# ULA.net
KiCad netlist of a schematic drawn in EAGLE
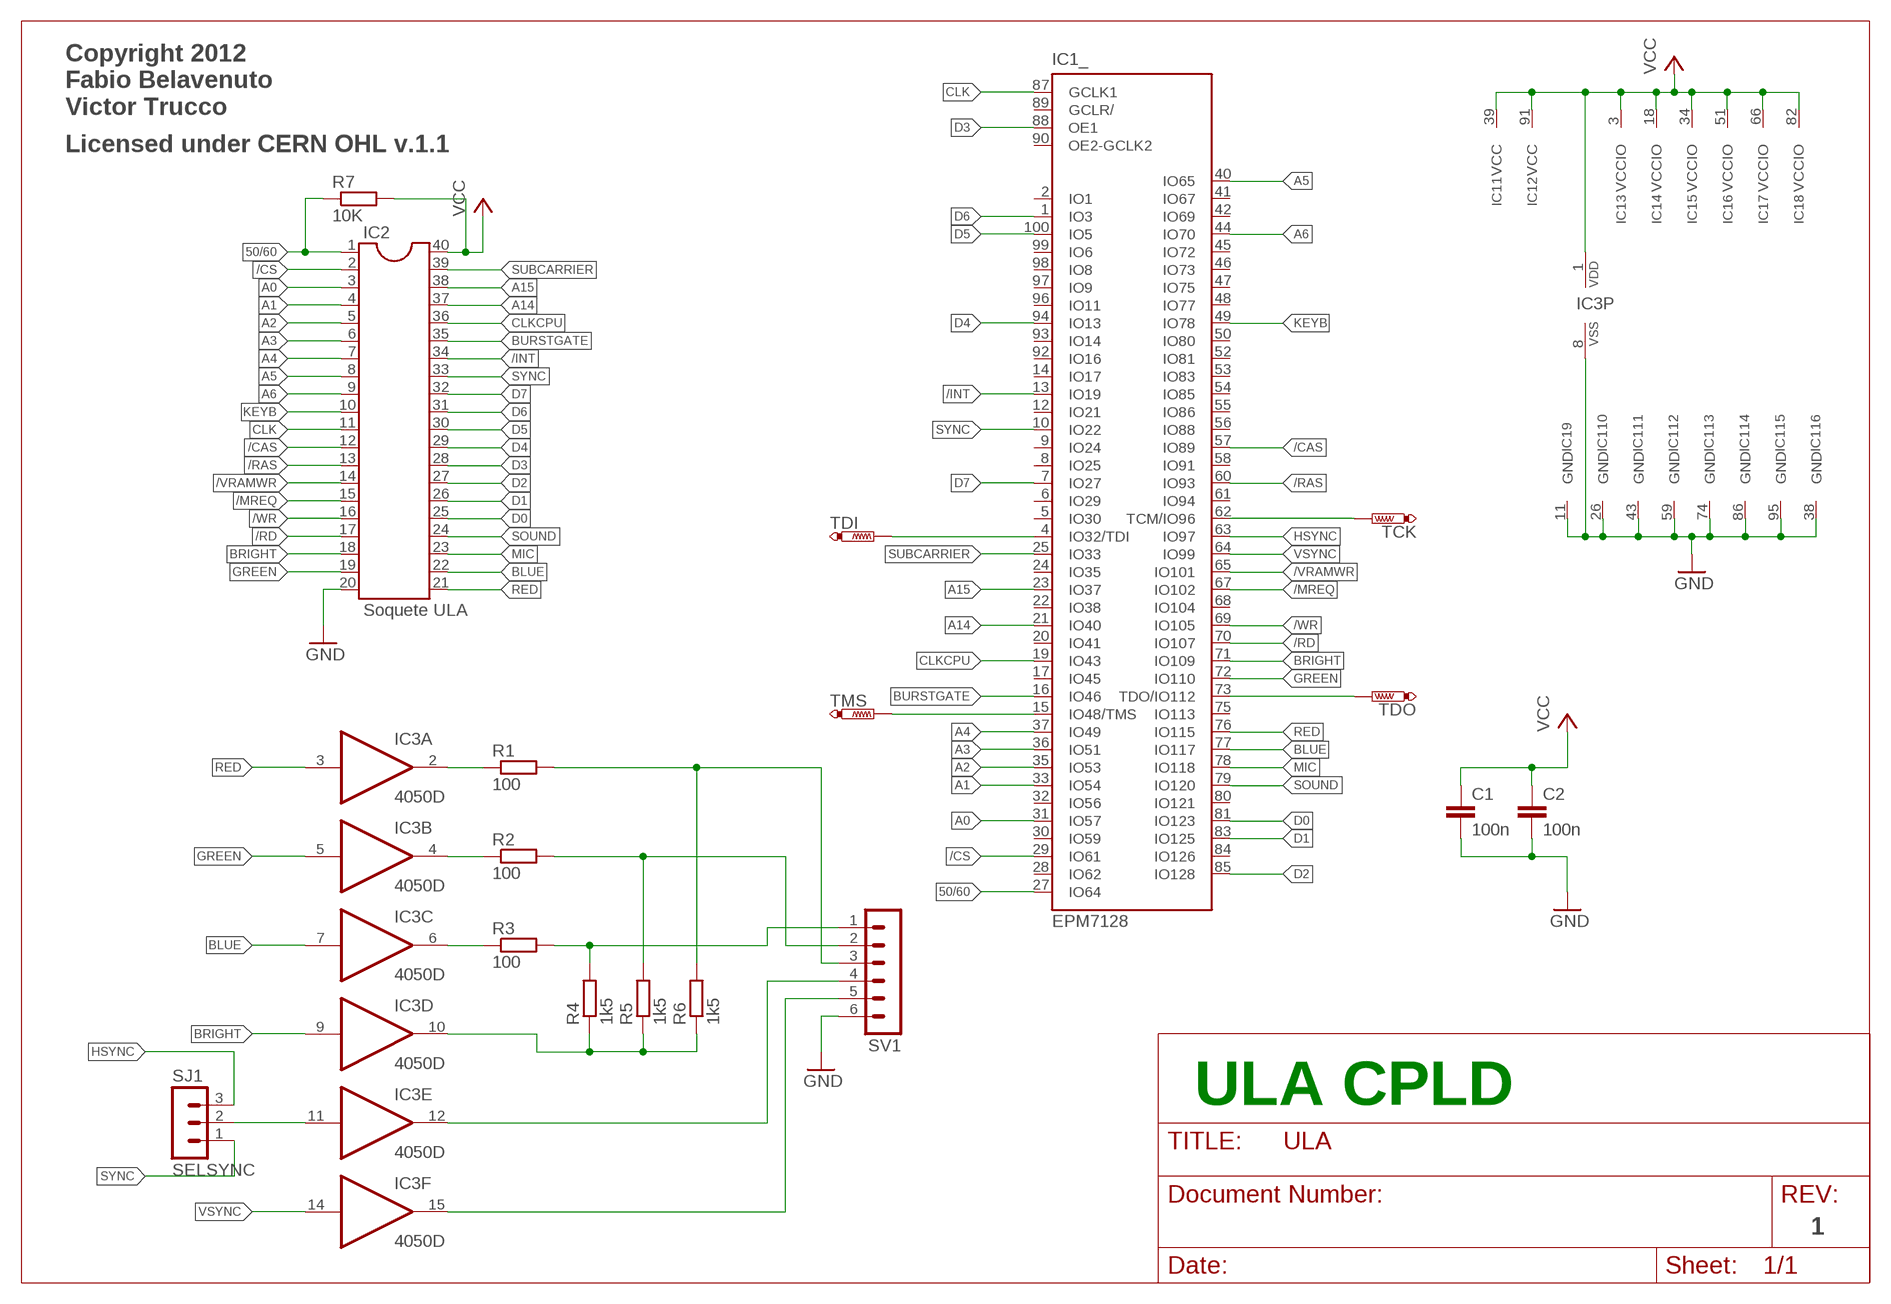
[diagram p0: schematic, sheet 1]

(export (version "E")
  (design (tool "Eeschema 10.0.6"))
  (components
    (comp (ref "C1")
      (value "100n")
      (footprint "eagle-import:C1206K")
      (libsource (lib "eagle-import") (part "C-EUC1206K"))
    )
    (comp (ref "C2")
      (value "100n")
      (footprint "eagle-import:C1206K")
      (libsource (lib "eagle-import") (part "C-EUC1206K"))
    )
    (comp (ref "IC1")
      (value "EPM7128")
      (footprint "eagle-import:TQFP100")
      (fields (field (name "MPN") "EPM7128STC100-7N"))
      (libsource (lib "eagle-import") (part "EPM7128-?100T"))
    )
    (comp (ref "IC2")
      (value "Soquete ULA")
      (footprint "eagle-import:DIL40")
      (libsource (lib "eagle-import") (part "DIL40"))
    )
    (comp (ref "IC3")
      (value "4050D")
      (footprint "eagle-import:SO16")
      (libsource (lib "eagle-import") (part "4050D"))
    )
    (comp (ref "R1")
      (value "100")
      (footprint "eagle-import:M0805")
      (libsource (lib "eagle-import") (part "R-EU_M0805"))
    )
    (comp (ref "R2")
      (value "100")
      (footprint "eagle-import:M0805")
      (libsource (lib "eagle-import") (part "R-EU_M0805"))
    )
    (comp (ref "R3")
      (value "100")
      (footprint "eagle-import:M0805")
      (libsource (lib "eagle-import") (part "R-EU_M0805"))
    )
    (comp (ref "R4")
      (value "1k5")
      (footprint "eagle-import:M0805")
      (libsource (lib "eagle-import") (part "R-EU_M0805"))
    )
    (comp (ref "R5")
      (value "1k5")
      (footprint "eagle-import:M0805")
      (libsource (lib "eagle-import") (part "R-EU_M0805"))
    )
    (comp (ref "R6")
      (value "1k5")
      (footprint "eagle-import:M0805")
      (libsource (lib "eagle-import") (part "R-EU_M0805"))
    )
    (comp (ref "R7")
      (value "10K")
      (footprint "eagle-import:M0805")
      (libsource (lib "eagle-import") (part "R-EU_M0805"))
    )
    (comp (ref "SJ1")
      (value "SELSYNC")
      (footprint "eagle-import:MA03-1-1")
      (libsource (lib "eagle-import") (part "MA03-1MA03-1-1"))
    )
    (comp (ref "SV1")
      (value "MA06-11")
      (footprint "eagle-import:MA06-1-1")
      (libsource (lib "eagle-import") (part "MA06-11"))
    )
    (comp (ref "TCK")
      (value "PTR1PAD1-10")
      (footprint "eagle-import:P1-10")
      (libsource (lib "eagle-import") (part "PTR1PAD1-10"))
    )
    (comp (ref "TDI")
      (value "PTR1PAD1-10")
      (footprint "eagle-import:P1-10")
      (libsource (lib "eagle-import") (part "PTR1PAD1-10"))
    )
    (comp (ref "TDO")
      (value "PTR1PAD1-10")
      (footprint "eagle-import:P1-10")
      (libsource (lib "eagle-import") (part "PTR1PAD1-10"))
    )
    (comp (ref "TMS")
      (value "PTR1PAD1-10")
      (footprint "eagle-import:P1-10")
      (libsource (lib "eagle-import") (part "PTR1PAD1-10"))
    )
  )
  (nets
    (net (code "1") (name "50{slash}60") (class "Default")
      (node (ref "IC1") (pin "27") (pinfunction "IO64_27") (pintype "bidirectional"))
      (node (ref "IC2") (pin "1") (pinfunction "1_1") (pintype "passive"))
      (node (ref "R7") (pin "1") (pinfunction "1_1") (pintype "passive"))
    )
    (net (code "2") (name "A0") (class "Default")
      (node (ref "IC1") (pin "31") (pinfunction "IO57_31") (pintype "bidirectional"))
      (node (ref "IC2") (pin "3") (pinfunction "3_3") (pintype "passive"))
    )
    (net (code "3") (name "A1") (class "Default")
      (node (ref "IC1") (pin "33") (pinfunction "IO54_33") (pintype "bidirectional"))
      (node (ref "IC2") (pin "4") (pinfunction "4_4") (pintype "passive"))
    )
    (net (code "4") (name "A2") (class "Default")
      (node (ref "IC1") (pin "35") (pinfunction "IO53_35") (pintype "bidirectional"))
      (node (ref "IC2") (pin "5") (pinfunction "5_5") (pintype "passive"))
    )
    (net (code "5") (name "A3") (class "Default")
      (node (ref "IC1") (pin "36") (pinfunction "IO51_36") (pintype "bidirectional"))
      (node (ref "IC2") (pin "6") (pinfunction "6_6") (pintype "passive"))
    )
    (net (code "6") (name "A4") (class "Default")
      (node (ref "IC1") (pin "37") (pinfunction "IO49_37") (pintype "bidirectional"))
      (node (ref "IC2") (pin "7") (pinfunction "7_7") (pintype "passive"))
    )
    (net (code "7") (name "A5") (class "Default")
      (node (ref "IC1") (pin "40") (pinfunction "IO65_40") (pintype "bidirectional"))
      (node (ref "IC2") (pin "8") (pinfunction "8_8") (pintype "passive"))
    )
    (net (code "8") (name "A6") (class "Default")
      (node (ref "IC1") (pin "44") (pinfunction "IO70_44") (pintype "bidirectional"))
      (node (ref "IC2") (pin "9") (pinfunction "9_9") (pintype "passive"))
    )
    (net (code "9") (name "A14") (class "Default")
      (node (ref "IC1") (pin "21") (pinfunction "IO40_21") (pintype "bidirectional"))
      (node (ref "IC2") (pin "37") (pinfunction "37_37") (pintype "passive"))
    )
    (net (code "10") (name "A15") (class "Default")
      (node (ref "IC1") (pin "23") (pinfunction "IO37_23") (pintype "bidirectional"))
      (node (ref "IC2") (pin "38") (pinfunction "38_38") (pintype "passive"))
    )
    (net (code "11") (name "BLUE") (class "Default")
      (node (ref "IC1") (pin "77") (pinfunction "IO117_77") (pintype "bidirectional"))
      (node (ref "IC2") (pin "22") (pinfunction "22_22") (pintype "passive"))
      (node (ref "IC3") (pin "7") (pinfunction "I_7") (pintype "input"))
    )
    (net (code "12") (name "BRIGHT") (class "Default")
      (node (ref "IC1") (pin "71") (pinfunction "IO109_71") (pintype "bidirectional"))
      (node (ref "IC2") (pin "18") (pinfunction "18_18") (pintype "passive"))
      (node (ref "IC3") (pin "9") (pinfunction "I_9") (pintype "input"))
    )
    (net (code "13") (name "BURSTGATE") (class "Default")
      (node (ref "IC1") (pin "16") (pinfunction "IO46_16") (pintype "bidirectional"))
      (node (ref "IC2") (pin "35") (pinfunction "35_35") (pintype "passive"))
    )
    (net (code "14") (name "CLK") (class "Default")
      (node (ref "IC1") (pin "87") (pinfunction "GCLK1_87") (pintype "input"))
      (node (ref "IC2") (pin "11") (pinfunction "11_11") (pintype "passive"))
    )
    (net (code "15") (name "CLKCPU") (class "Default")
      (node (ref "IC1") (pin "19") (pinfunction "IO43_19") (pintype "bidirectional"))
      (node (ref "IC2") (pin "36") (pinfunction "36_36") (pintype "passive"))
    )
    (net (code "16") (name "D0") (class "Default")
      (node (ref "IC1") (pin "81") (pinfunction "IO123_81") (pintype "bidirectional"))
      (node (ref "IC2") (pin "25") (pinfunction "25_25") (pintype "passive"))
    )
    (net (code "17") (name "D1") (class "Default")
      (node (ref "IC1") (pin "83") (pinfunction "IO125_83") (pintype "bidirectional"))
      (node (ref "IC2") (pin "26") (pinfunction "26_26") (pintype "passive"))
    )
    (net (code "18") (name "D2") (class "Default")
      (node (ref "IC1") (pin "85") (pinfunction "IO128_85") (pintype "bidirectional"))
      (node (ref "IC2") (pin "27") (pinfunction "27_27") (pintype "passive"))
    )
    (net (code "19") (name "D3") (class "Default")
      (node (ref "IC1") (pin "88") (pinfunction "OE1_88") (pintype "input"))
      (node (ref "IC2") (pin "28") (pinfunction "28_28") (pintype "passive"))
    )
    (net (code "20") (name "D4") (class "Default")
      (node (ref "IC1") (pin "94") (pinfunction "IO13_94") (pintype "bidirectional"))
      (node (ref "IC2") (pin "29") (pinfunction "29_29") (pintype "passive"))
    )
    (net (code "21") (name "D5") (class "Default")
      (node (ref "IC1") (pin "100") (pinfunction "IO5_100") (pintype "bidirectional"))
      (node (ref "IC2") (pin "30") (pinfunction "30_30") (pintype "passive"))
    )
    (net (code "22") (name "D6") (class "Default")
      (node (ref "IC1") (pin "1") (pinfunction "IO3_1") (pintype "bidirectional"))
      (node (ref "IC2") (pin "31") (pinfunction "31_31") (pintype "passive"))
    )
    (net (code "23") (name "D7") (class "Default")
      (node (ref "IC1") (pin "7") (pinfunction "IO27_7") (pintype "bidirectional"))
      (node (ref "IC2") (pin "32") (pinfunction "32_32") (pintype "passive"))
    )
    (net (code "24") (name "GND") (class "Default")
      (node (ref "C1") (pin "2") (pinfunction "2_2") (pintype "passive"))
      (node (ref "C2") (pin "2") (pinfunction "2_2") (pintype "passive"))
      (node (ref "IC1") (pin "11") (pinfunction "GND_11") (pintype "power_in"))
      (node (ref "IC1") (pin "26") (pinfunction "GND_26") (pintype "power_in"))
      (node (ref "IC1") (pin "38") (pinfunction "GND_38") (pintype "power_in"))
      (node (ref "IC1") (pin "43") (pinfunction "GND_43") (pintype "power_in"))
      (node (ref "IC1") (pin "59") (pinfunction "GND_59") (pintype "power_in"))
      (node (ref "IC1") (pin "74") (pinfunction "GND_74") (pintype "power_in"))
      (node (ref "IC1") (pin "86") (pinfunction "GND_86") (pintype "power_in"))
      (node (ref "IC1") (pin "95") (pinfunction "GND_95") (pintype "power_in"))
      (node (ref "IC2") (pin "20") (pinfunction "20_20") (pintype "passive"))
      (node (ref "IC3") (pin "8") (pinfunction "VSS_8") (pintype "power_in"))
      (node (ref "SV1") (pin "6") (pinfunction "6_6") (pintype "passive"))
    )
    (net (code "25") (name "GREEN") (class "Default")
      (node (ref "IC1") (pin "72") (pinfunction "IO110_72") (pintype "bidirectional"))
      (node (ref "IC2") (pin "19") (pinfunction "19_19") (pintype "passive"))
      (node (ref "IC3") (pin "5") (pinfunction "I_5") (pintype "input"))
    )
    (net (code "26") (name "HSYNC") (class "Default")
      (node (ref "IC1") (pin "63") (pinfunction "IO97_63") (pintype "bidirectional"))
      (node (ref "SJ1") (pin "3") (pinfunction "3_3") (pintype "passive"))
    )
    (net (code "27") (name "KEYB") (class "Default")
      (node (ref "IC1") (pin "49") (pinfunction "IO78_49") (pintype "bidirectional"))
      (node (ref "IC2") (pin "10") (pinfunction "10_10") (pintype "passive"))
    )
    (net (code "28") (name "MIC") (class "Default")
      (node (ref "IC1") (pin "78") (pinfunction "IO118_78") (pintype "bidirectional"))
      (node (ref "IC2") (pin "23") (pinfunction "23_23") (pintype "passive"))
    )
    (net (code "29") (name "Net-(IC1Q-IO32{slash}TDI)") (class "Default")
      (node (ref "IC1") (pin "4") (pinfunction "IO32/TDI_4") (pintype "bidirectional"))
      (node (ref "TDI") (pin "TP") (pinfunction "TP_TP") (pintype "input"))
    )
    (net (code "30") (name "Net-(IC1Q-IO48{slash}TMS)") (class "Default")
      (node (ref "IC1") (pin "15") (pinfunction "IO48/TMS_15") (pintype "bidirectional"))
      (node (ref "TMS") (pin "TP") (pinfunction "TP_TP") (pintype "input"))
    )
    (net (code "31") (name "Net-(IC1Q-TCM{slash}IO96)") (class "Default")
      (node (ref "IC1") (pin "62") (pinfunction "TCM/IO96_62") (pintype "bidirectional"))
      (node (ref "TCK") (pin "TP") (pinfunction "TP_TP") (pintype "input"))
    )
    (net (code "32") (name "Net-(IC1Q-TDO{slash}IO112)") (class "Default")
      (node (ref "IC1") (pin "73") (pinfunction "TDO/IO112_73") (pintype "bidirectional"))
      (node (ref "TDO") (pin "TP") (pinfunction "TP_TP") (pintype "input"))
    )
    (net (code "33") (name "Net-(IC3A-O)") (class "Default")
      (node (ref "IC3") (pin "2") (pinfunction "O_2") (pintype "output"))
      (node (ref "R1") (pin "1") (pinfunction "1_1") (pintype "passive"))
    )
    (net (code "34") (name "Net-(IC3B-O)") (class "Default")
      (node (ref "IC3") (pin "4") (pinfunction "O_4") (pintype "output"))
      (node (ref "R2") (pin "1") (pinfunction "1_1") (pintype "passive"))
    )
    (net (code "35") (name "Net-(IC3C-O)") (class "Default")
      (node (ref "IC3") (pin "6") (pinfunction "O_6") (pintype "output"))
      (node (ref "R3") (pin "1") (pinfunction "1_1") (pintype "passive"))
    )
    (net (code "36") (name "Net-(IC3D-O)") (class "Default")
      (node (ref "IC3") (pin "10") (pinfunction "O_10") (pintype "output"))
      (node (ref "R4") (pin "1") (pinfunction "1_1") (pintype "passive"))
      (node (ref "R5") (pin "1") (pinfunction "1_1") (pintype "passive"))
      (node (ref "R6") (pin "1") (pinfunction "1_1") (pintype "passive"))
    )
    (net (code "37") (name "Net-(IC3E-I)") (class "Default")
      (node (ref "IC3") (pin "11") (pinfunction "I_11") (pintype "input"))
      (node (ref "SJ1") (pin "2") (pinfunction "2_2") (pintype "passive"))
    )
    (net (code "38") (name "Net-(IC3E-O)") (class "Default")
      (node (ref "IC3") (pin "12") (pinfunction "O_12") (pintype "output"))
      (node (ref "SV1") (pin "4") (pinfunction "4_4") (pintype "passive"))
    )
    (net (code "39") (name "Net-(IC3F-O)") (class "Default")
      (node (ref "IC3") (pin "15") (pinfunction "O_15") (pintype "output"))
      (node (ref "SV1") (pin "5") (pinfunction "5_5") (pintype "passive"))
    )
    (net (code "40") (name "Net-(R1-Pad2)") (class "Default")
      (node (ref "R1") (pin "2") (pinfunction "2_2") (pintype "passive"))
      (node (ref "R6") (pin "2") (pinfunction "2_2") (pintype "passive"))
      (node (ref "SV1") (pin "3") (pinfunction "3_3") (pintype "passive"))
    )
    (net (code "41") (name "Net-(R2-Pad2)") (class "Default")
      (node (ref "R2") (pin "2") (pinfunction "2_2") (pintype "passive"))
      (node (ref "R5") (pin "2") (pinfunction "2_2") (pintype "passive"))
      (node (ref "SV1") (pin "2") (pinfunction "2_2") (pintype "passive"))
    )
    (net (code "42") (name "Net-(R3-Pad2)") (class "Default")
      (node (ref "R3") (pin "2") (pinfunction "2_2") (pintype "passive"))
      (node (ref "R4") (pin "2") (pinfunction "2_2") (pintype "passive"))
      (node (ref "SV1") (pin "1") (pinfunction "1_1") (pintype "passive"))
    )
    (net (code "43") (name "RED") (class "Default")
      (node (ref "IC1") (pin "76") (pinfunction "IO115_76") (pintype "bidirectional"))
      (node (ref "IC2") (pin "21") (pinfunction "21_21") (pintype "passive"))
      (node (ref "IC3") (pin "3") (pinfunction "I_3") (pintype "input"))
    )
    (net (code "44") (name "SOUND") (class "Default")
      (node (ref "IC1") (pin "79") (pinfunction "IO120_79") (pintype "bidirectional"))
      (node (ref "IC2") (pin "24") (pinfunction "24_24") (pintype "passive"))
    )
    (net (code "45") (name "SUBCARRIER") (class "Default")
      (node (ref "IC1") (pin "25") (pinfunction "IO33_25") (pintype "bidirectional"))
      (node (ref "IC2") (pin "39") (pinfunction "39_39") (pintype "passive"))
    )
    (net (code "46") (name "SYNC") (class "Default")
      (node (ref "IC1") (pin "10") (pinfunction "IO22_10") (pintype "bidirectional"))
      (node (ref "IC2") (pin "33") (pinfunction "33_33") (pintype "passive"))
      (node (ref "SJ1") (pin "1") (pinfunction "1_1") (pintype "passive"))
    )
    (net (code "47") (name "VCC") (class "Default")
      (node (ref "C1") (pin "1") (pinfunction "1_1") (pintype "passive"))
      (node (ref "C2") (pin "1") (pinfunction "1_1") (pintype "passive"))
      (node (ref "IC1") (pin "18") (pinfunction "VCCIO_18") (pintype "power_in"))
      (node (ref "IC1") (pin "3") (pinfunction "VCCIO_3") (pintype "power_in"))
      (node (ref "IC1") (pin "34") (pinfunction "VCCIO_34") (pintype "power_in"))
      (node (ref "IC1") (pin "39") (pinfunction "VCC_39") (pintype "power_in"))
      (node (ref "IC1") (pin "51") (pinfunction "VCCIO_51") (pintype "power_in"))
      (node (ref "IC1") (pin "66") (pinfunction "VCCIO_66") (pintype "power_in"))
      (node (ref "IC1") (pin "82") (pinfunction "VCCIO_82") (pintype "power_in"))
      (node (ref "IC1") (pin "91") (pinfunction "VCC_91") (pintype "power_in"))
      (node (ref "IC2") (pin "40") (pinfunction "40_40") (pintype "passive"))
      (node (ref "IC3") (pin "1") (pinfunction "VDD_1") (pintype "power_in"))
      (node (ref "R7") (pin "2") (pinfunction "2_2") (pintype "passive"))
    )
    (net (code "48") (name "VSYNC") (class "Default")
      (node (ref "IC1") (pin "64") (pinfunction "IO99_64") (pintype "bidirectional"))
      (node (ref "IC3") (pin "14") (pinfunction "I_14") (pintype "input"))
    )
    (net (code "49") (name "unconnected-(IC1Q-GCLR{slash}-Pad89)") (class "Default")
      (node (ref "IC1") (pin "89") (pinfunction "GCLR/_89") (pintype "input"))
    )
    (net (code "50") (name "unconnected-(IC1Q-IO1-Pad2)") (class "Default")
      (node (ref "IC1") (pin "2") (pinfunction "IO1_2") (pintype "bidirectional"))
    )
    (net (code "51") (name "unconnected-(IC1Q-IO6-Pad99)") (class "Default")
      (node (ref "IC1") (pin "99") (pinfunction "IO6_99") (pintype "bidirectional"))
    )
    (net (code "52") (name "unconnected-(IC1Q-IO8-Pad98)") (class "Default")
      (node (ref "IC1") (pin "98") (pinfunction "IO8_98") (pintype "bidirectional"))
    )
    (net (code "53") (name "unconnected-(IC1Q-IO9-Pad97)") (class "Default")
      (node (ref "IC1") (pin "97") (pinfunction "IO9_97") (pintype "bidirectional"))
    )
    (net (code "54") (name "unconnected-(IC1Q-IO11-Pad96)") (class "Default")
      (node (ref "IC1") (pin "96") (pinfunction "IO11_96") (pintype "bidirectional"))
    )
    (net (code "55") (name "unconnected-(IC1Q-IO14-Pad93)") (class "Default")
      (node (ref "IC1") (pin "93") (pinfunction "IO14_93") (pintype "bidirectional"))
    )
    (net (code "56") (name "unconnected-(IC1Q-IO16-Pad92)") (class "Default")
      (node (ref "IC1") (pin "92") (pinfunction "IO16_92") (pintype "bidirectional"))
    )
    (net (code "57") (name "unconnected-(IC1Q-IO17-Pad14)") (class "Default")
      (node (ref "IC1") (pin "14") (pinfunction "IO17_14") (pintype "bidirectional"))
    )
    (net (code "58") (name "unconnected-(IC1Q-IO21-Pad12)") (class "Default")
      (node (ref "IC1") (pin "12") (pinfunction "IO21_12") (pintype "bidirectional"))
    )
    (net (code "59") (name "unconnected-(IC1Q-IO24-Pad9)") (class "Default")
      (node (ref "IC1") (pin "9") (pinfunction "IO24_9") (pintype "bidirectional"))
    )
    (net (code "60") (name "unconnected-(IC1Q-IO25-Pad8)") (class "Default")
      (node (ref "IC1") (pin "8") (pinfunction "IO25_8") (pintype "bidirectional"))
    )
    (net (code "61") (name "unconnected-(IC1Q-IO29-Pad6)") (class "Default")
      (node (ref "IC1") (pin "6") (pinfunction "IO29_6") (pintype "bidirectional"))
    )
    (net (code "62") (name "unconnected-(IC1Q-IO30-Pad5)") (class "Default")
      (node (ref "IC1") (pin "5") (pinfunction "IO30_5") (pintype "bidirectional"))
    )
    (net (code "63") (name "unconnected-(IC1Q-IO35-Pad24)") (class "Default")
      (node (ref "IC1") (pin "24") (pinfunction "IO35_24") (pintype "bidirectional"))
    )
    (net (code "64") (name "unconnected-(IC1Q-IO38-Pad22)") (class "Default")
      (node (ref "IC1") (pin "22") (pinfunction "IO38_22") (pintype "bidirectional"))
    )
    (net (code "65") (name "unconnected-(IC1Q-IO41-Pad20)") (class "Default")
      (node (ref "IC1") (pin "20") (pinfunction "IO41_20") (pintype "bidirectional"))
    )
    (net (code "66") (name "unconnected-(IC1Q-IO45-Pad17)") (class "Default")
      (node (ref "IC1") (pin "17") (pinfunction "IO45_17") (pintype "bidirectional"))
    )
    (net (code "67") (name "unconnected-(IC1Q-IO56-Pad32)") (class "Default")
      (node (ref "IC1") (pin "32") (pinfunction "IO56_32") (pintype "bidirectional"))
    )
    (net (code "68") (name "unconnected-(IC1Q-IO59-Pad30)") (class "Default")
      (node (ref "IC1") (pin "30") (pinfunction "IO59_30") (pintype "bidirectional"))
    )
    (net (code "69") (name "unconnected-(IC1Q-IO62-Pad28)") (class "Default")
      (node (ref "IC1") (pin "28") (pinfunction "IO62_28") (pintype "bidirectional"))
    )
    (net (code "70") (name "unconnected-(IC1Q-IO67-Pad41)") (class "Default")
      (node (ref "IC1") (pin "41") (pinfunction "IO67_41") (pintype "bidirectional"))
    )
    (net (code "71") (name "unconnected-(IC1Q-IO69-Pad42)") (class "Default")
      (node (ref "IC1") (pin "42") (pinfunction "IO69_42") (pintype "bidirectional"))
    )
    (net (code "72") (name "unconnected-(IC1Q-IO72-Pad45)") (class "Default")
      (node (ref "IC1") (pin "45") (pinfunction "IO72_45") (pintype "bidirectional"))
    )
    (net (code "73") (name "unconnected-(IC1Q-IO73-Pad46)") (class "Default")
      (node (ref "IC1") (pin "46") (pinfunction "IO73_46") (pintype "bidirectional"))
    )
    (net (code "74") (name "unconnected-(IC1Q-IO75-Pad47)") (class "Default")
      (node (ref "IC1") (pin "47") (pinfunction "IO75_47") (pintype "bidirectional"))
    )
    (net (code "75") (name "unconnected-(IC1Q-IO77-Pad48)") (class "Default")
      (node (ref "IC1") (pin "48") (pinfunction "IO77_48") (pintype "bidirectional"))
    )
    (net (code "76") (name "unconnected-(IC1Q-IO80-Pad50)") (class "Default")
      (node (ref "IC1") (pin "50") (pinfunction "IO80_50") (pintype "bidirectional"))
    )
    (net (code "77") (name "unconnected-(IC1Q-IO81-Pad52)") (class "Default")
      (node (ref "IC1") (pin "52") (pinfunction "IO81_52") (pintype "bidirectional"))
    )
    (net (code "78") (name "unconnected-(IC1Q-IO83-Pad53)") (class "Default")
      (node (ref "IC1") (pin "53") (pinfunction "IO83_53") (pintype "bidirectional"))
    )
    (net (code "79") (name "unconnected-(IC1Q-IO85-Pad54)") (class "Default")
      (node (ref "IC1") (pin "54") (pinfunction "IO85_54") (pintype "bidirectional"))
    )
    (net (code "80") (name "unconnected-(IC1Q-IO86-Pad55)") (class "Default")
      (node (ref "IC1") (pin "55") (pinfunction "IO86_55") (pintype "bidirectional"))
    )
    (net (code "81") (name "unconnected-(IC1Q-IO88-Pad56)") (class "Default")
      (node (ref "IC1") (pin "56") (pinfunction "IO88_56") (pintype "bidirectional"))
    )
    (net (code "82") (name "unconnected-(IC1Q-IO91-Pad58)") (class "Default")
      (node (ref "IC1") (pin "58") (pinfunction "IO91_58") (pintype "bidirectional"))
    )
    (net (code "83") (name "unconnected-(IC1Q-IO94-Pad61)") (class "Default")
      (node (ref "IC1") (pin "61") (pinfunction "IO94_61") (pintype "bidirectional"))
    )
    (net (code "84") (name "unconnected-(IC1Q-IO104-Pad68)") (class "Default")
      (node (ref "IC1") (pin "68") (pinfunction "IO104_68") (pintype "bidirectional"))
    )
    (net (code "85") (name "unconnected-(IC1Q-IO113-Pad75)") (class "Default")
      (node (ref "IC1") (pin "75") (pinfunction "IO113_75") (pintype "bidirectional"))
    )
    (net (code "86") (name "unconnected-(IC1Q-IO121-Pad80)") (class "Default")
      (node (ref "IC1") (pin "80") (pinfunction "IO121_80") (pintype "bidirectional"))
    )
    (net (code "87") (name "unconnected-(IC1Q-IO126-Pad84)") (class "Default")
      (node (ref "IC1") (pin "84") (pinfunction "IO126_84") (pintype "bidirectional"))
    )
    (net (code "88") (name "unconnected-(IC1Q-OE2-GCLK2-Pad90)") (class "Default")
      (node (ref "IC1") (pin "90") (pinfunction "OE2-GCLK2_90") (pintype "input"))
    )
    (net (code "89") (name "{slash}CAS") (class "Default")
      (node (ref "IC1") (pin "57") (pinfunction "IO89_57") (pintype "bidirectional"))
      (node (ref "IC2") (pin "12") (pinfunction "12_12") (pintype "passive"))
    )
    (net (code "90") (name "{slash}CS") (class "Default")
      (node (ref "IC1") (pin "29") (pinfunction "IO61_29") (pintype "bidirectional"))
      (node (ref "IC2") (pin "2") (pinfunction "2_2") (pintype "passive"))
    )
    (net (code "91") (name "{slash}INT") (class "Default")
      (node (ref "IC1") (pin "13") (pinfunction "IO19_13") (pintype "bidirectional"))
      (node (ref "IC2") (pin "34") (pinfunction "34_34") (pintype "passive"))
    )
    (net (code "92") (name "{slash}MREQ") (class "Default")
      (node (ref "IC1") (pin "67") (pinfunction "IO102_67") (pintype "bidirectional"))
      (node (ref "IC2") (pin "15") (pinfunction "15_15") (pintype "passive"))
    )
    (net (code "93") (name "{slash}RAS") (class "Default")
      (node (ref "IC1") (pin "60") (pinfunction "IO93_60") (pintype "bidirectional"))
      (node (ref "IC2") (pin "13") (pinfunction "13_13") (pintype "passive"))
    )
    (net (code "94") (name "{slash}RD") (class "Default")
      (node (ref "IC1") (pin "70") (pinfunction "IO107_70") (pintype "bidirectional"))
      (node (ref "IC2") (pin "17") (pinfunction "17_17") (pintype "passive"))
    )
    (net (code "95") (name "{slash}VRAMWR") (class "Default")
      (node (ref "IC1") (pin "65") (pinfunction "IO101_65") (pintype "bidirectional"))
      (node (ref "IC2") (pin "14") (pinfunction "14_14") (pintype "passive"))
    )
    (net (code "96") (name "{slash}WR") (class "Default")
      (node (ref "IC1") (pin "69") (pinfunction "IO105_69") (pintype "bidirectional"))
      (node (ref "IC2") (pin "16") (pinfunction "16_16") (pintype "passive"))
    )
  )
)
